# MCU.net
KiCad netlist of a schematic drawn in Altium Designer
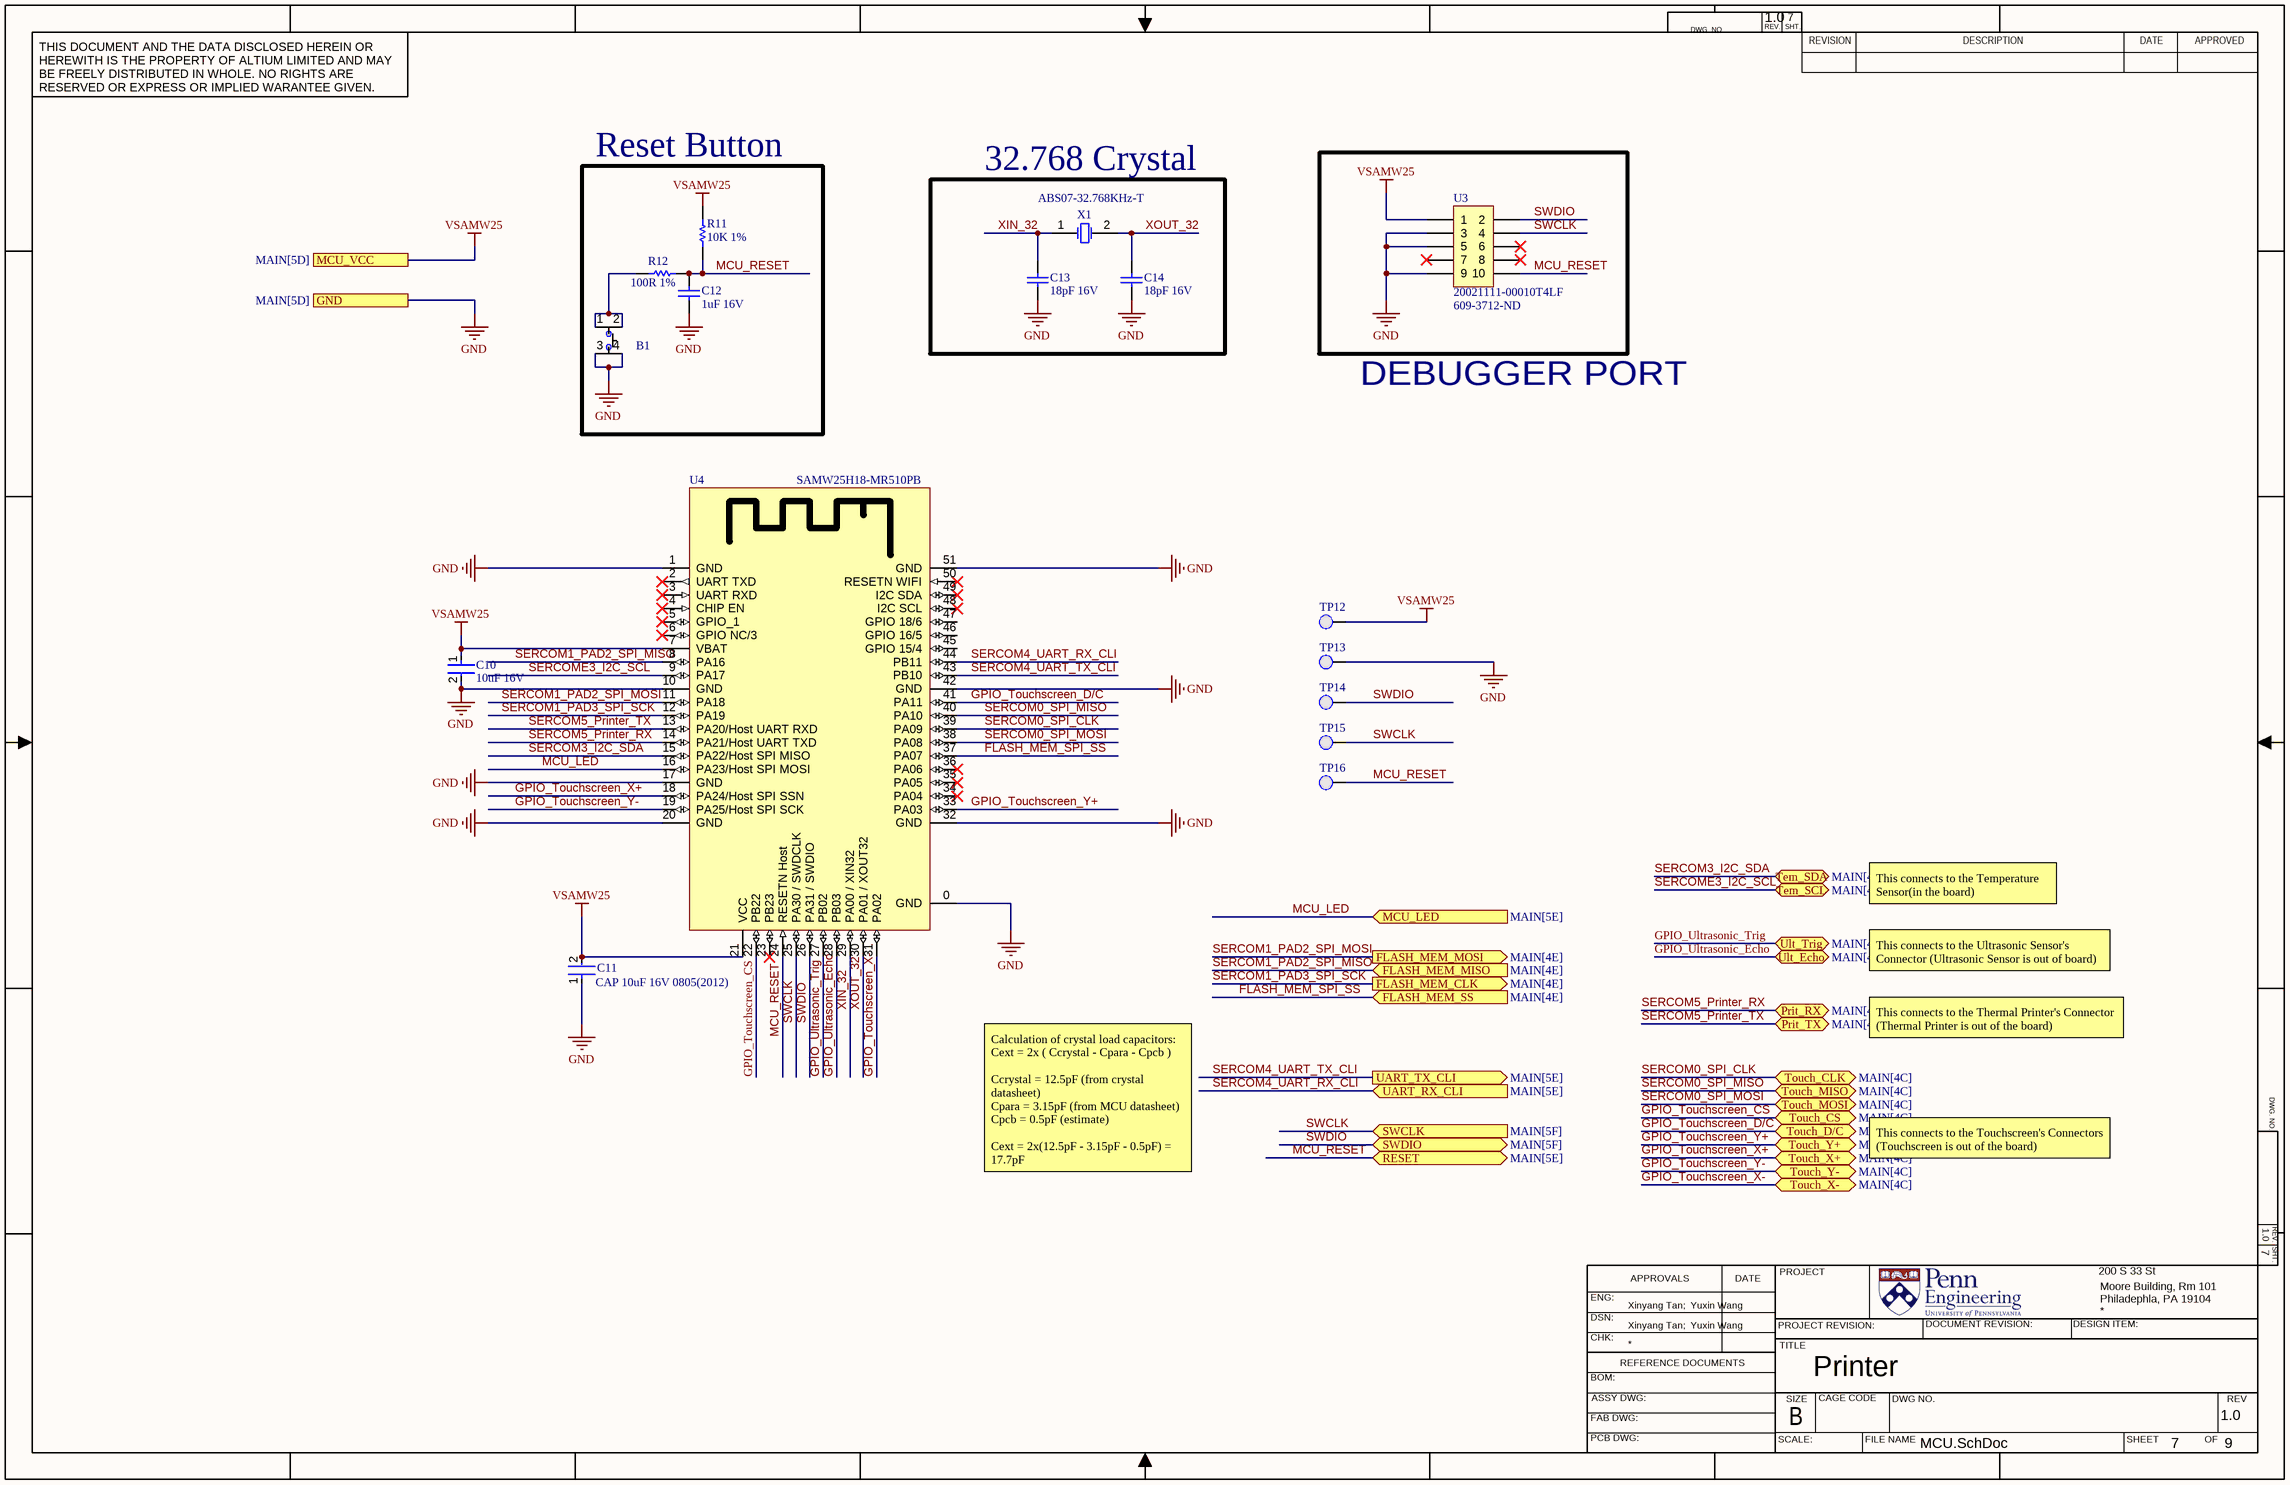
[diagram p0: MCU.SchDoc]

(export (version "E")
  (design (tool "Eeschema 10.0.6"))
  (components
    (comp (ref "B1")
      (value "PTS810 SJK 250 SMTR LFS")
      (footprint "PTS810 SJK 250 SMTR LFS")
      (description "SWITCH TACTILE SPST-NO 0.05A 16V Tactile Switch SPST-NO Top Actuated Surface Mount")
      (fields
        (field (name "MANUFACTURER") "ITT /  C&K Components")
        (field (name "MANUFACTURER PART NUMBER") "PTS810SJK250SMTRLFS")
      )
      (libsource (lib "Schematics") (part "PTS810 SJK 250 SMTR LFS"))
    )
    (comp (ref "C10")
      (value "10uF 16V")
      (footprint "FP-0805-L_2_01_0_2-W_1_25-IPC_A")
      (description "General Purpose Ceramic Capacitor, 0805, 10uF, 10%, X5R, 15%, 16V")
      (fields (field (name "TOLERANCE") "10%") (field (name "VOLTAGE") "16V"))
      (libsource (lib "Altium Content Vault") (part "02cd4be3c70576c341d710602a673aa"))
    )
    (comp (ref "C11")
      (value "CAP 10uF 16V 0805(2012)")
      (footprint "FP-0805-L_2_01_0_2-W_1_25-IPC_A")
      (description "General Purpose Ceramic Capacitor, 0805, 10uF, 10%, X5R, 15%, 16V")
      (fields (field (name "TOLERANCE") "10%") (field (name "VOLTAGE") "16V"))
      (libsource (lib "Altium Content Vault") (part "02cd4be3c70576c341d710602a673aa"))
    )
    (comp (ref "C12")
      (value "1uF 16V")
      (footprint "CAPC0603(1608)100_N")
      (description "CAP 1uF 16V ±5% 0603 (1608 Metric) Thickness 1mm SMD")
      (fields (field (name "TOLERANCE") "Â±5%"))
      (libsource (lib "Altium Content Vault") (part "CAP"))
    )
    (comp (ref "C13")
      (value "18pF 16V")
      (footprint "CAPC0603(1608)100_N")
      (description "CAP 18pF 16V ±5% 0603 (1608 Metric) Thickness 1mm SMD")
      (fields (field (name "TOLERANCE") "Â±5%"))
      (libsource (lib "Altium Content Vault") (part "CAP"))
    )
    (comp (ref "C14")
      (value "18pF 16V")
      (footprint "CAPC0603(1608)100_N")
      (description "CAP 18pF 16V ±5% 0603 (1608 Metric) Thickness 1mm SMD")
      (fields (field (name "TOLERANCE") "Â±5%"))
      (libsource (lib "Altium Content Vault") (part "CAP"))
    )
    (comp (ref "R11")
      (value "10K 1%")
      (footprint "RESC0603(1608)_N")
      (description "10K 0.1W 1% 0603 (1608 Metric)  SMD")
      (fields (field (name "POWER") "0.1 W") (field (name "TOLERANCE") "1 %"))
      (libsource (lib "Altium Content Vault") (part "RES"))
    )
    (comp (ref "R12")
      (value "100R 1%")
      (footprint "RESC0603(1608)_N")
      (description "100R 0.1W 1% 0603 (1608 Metric)  SMD")
      (fields (field (name "TOLERANCE") "1 %") (field (name "POWER") "0.1 W"))
      (libsource (lib "Altium Content Vault") (part "RES"))
    )
    (comp (ref "TP12")
      (value "0.1\" Pad")
      (footprint "PCBComponent")
      (libsource (lib "Schematics") (part "0.1{dblquote} Pad-A.4"))
    )
    (comp (ref "TP13")
      (value "0.1\" Pad")
      (footprint "PCBComponent")
      (libsource (lib "Schematics") (part "0.1{dblquote} Pad-A.4"))
    )
    (comp (ref "TP14")
      (value "0.1\" Pad")
      (footprint "PCBComponent")
      (libsource (lib "Schematics") (part "0.1{dblquote} Pad-A.4"))
    )
    (comp (ref "TP15")
      (value "0.1\" Pad")
      (footprint "PCBComponent")
      (libsource (lib "Schematics") (part "0.1{dblquote} Pad-A.4"))
    )
    (comp (ref "TP16")
      (value "0.1\" Pad")
      (footprint "PCBComponent")
      (libsource (lib "Schematics") (part "0.1{dblquote} Pad-A.4"))
    )
    (comp (ref "U3")
      (value "20021111-00010T4LF")
      (footprint "20021111-00010T4LF")
      (description "CONN HEADER 10POS UNSHD VERT T/H")
      (fields
        (field (name "MANUFACTURER") "Amphenol / FCI")
        (field (name "SUPPLIER PART NUMBER 1") "609-3712-ND")
      )
      (libsource (lib "Schematics") (part "20021111-00010T4LF"))
    )
    (comp (ref "U4")
      (value "SAMW25H18-MR510PB")
      (footprint "SAMW25H18-MR510PB")
      (description "RF TXRX MODULE WIFI TRACE ANT")
      (fields
        (field (name "MANUFACTURER") "Atmel")
        (field (name "MANUFACTURER PART NUMBER") "ATSAMW25H18-MR510PB")
      )
      (libsource (lib "Schematics") (part "SAMW25H18-MR510PB"))
    )
    (comp (ref "X1")
      (value "ABS07-32.768KHz-T")
      (footprint "ABRA-ABS07-2_V")
      (description "Crystal, 32.768 kHz, 12.5 pF, -40 to 85 degC, SMD Low Profile 3.2 x 1.5 x 0.9 mm, Tape and Reel")
      (fields (field (name "MANUFACTURER") "Abracon"))
      (libsource (lib "Altium Content Vault") (part "ABRA-ABS07-2"))
    )
  )
  (nets
    (net (code "1") (name "/FLASH_MEM_SPI_SS") (class "Default")
      (node (ref "U4") (pin "37") (pinfunction "PA07_37") (pintype "bidirectional"))
    )
    (net (code "2") (name "/GPIO_Touchscreen_CS") (class "Default")
      (node (ref "U4") (pin "22") (pinfunction "PB22_22") (pintype "bidirectional"))
    )
    (net (code "3") (name "/GPIO_Touchscreen_D{slash}C") (class "Default")
      (node (ref "U4") (pin "41") (pinfunction "PA11_41") (pintype "bidirectional"))
    )
    (net (code "4") (name "/GPIO_Touchscreen_X+") (class "Default")
      (node (ref "U4") (pin "18") (pinfunction "PA24/Host_SPI_SSN_18") (pintype "bidirectional"))
    )
    (net (code "5") (name "/GPIO_Touchscreen_X-") (class "Default")
      (node (ref "U4") (pin "31") (pinfunction "PA02_31") (pintype "bidirectional"))
    )
    (net (code "6") (name "/GPIO_Touchscreen_Y+") (class "Default")
      (node (ref "U4") (pin "33") (pinfunction "PA03_33") (pintype "bidirectional"))
    )
    (net (code "7") (name "/GPIO_Touchscreen_Y-") (class "Default")
      (node (ref "U4") (pin "19") (pinfunction "PA25/Host_SPI_SCK_19") (pintype "bidirectional"))
    )
    (net (code "8") (name "/GPIO_Ultrasonic_Echo") (class "Default")
      (node (ref "U4") (pin "28") (pinfunction "PB03_28") (pintype "bidirectional"))
    )
    (net (code "9") (name "/GPIO_Ultrasonic_Trig") (class "Default")
      (node (ref "U4") (pin "27") (pinfunction "PB02_27") (pintype "bidirectional"))
    )
    (net (code "10") (name "/MCU_LED") (class "Default")
      (node (ref "U4") (pin "16") (pinfunction "PA23/Host_SPI_MOSI_16") (pintype "bidirectional"))
    )
    (net (code "11") (name "/MCU_RESET") (class "Default")
      (node (ref "C12") (pin "2") (pinfunction "2_2") (pintype "passive"))
      (node (ref "R11") (pin "1") (pinfunction "1_1") (pintype "passive"))
      (node (ref "R12") (pin "2") (pinfunction "2_2") (pintype "passive"))
      (node (ref "TP16") (pin "1") (pinfunction "PAD_1") (pintype "passive"))
      (node (ref "U3") (pin "10") (pinfunction "10_10") (pintype "passive"))
      (node (ref "U4") (pin "24") (pinfunction "RESETN_Host_24") (pintype "input"))
    )
    (net (code "12") (name "/SERCOM0_SPI_CLK") (class "Default")
      (node (ref "U4") (pin "39") (pinfunction "PA09_39") (pintype "bidirectional"))
    )
    (net (code "13") (name "/SERCOM0_SPI_MISO") (class "Default")
      (node (ref "U4") (pin "40") (pinfunction "PA10_40") (pintype "bidirectional"))
    )
    (net (code "14") (name "/SERCOM0_SPI_MOSI") (class "Default")
      (node (ref "U4") (pin "38") (pinfunction "PA08_38") (pintype "bidirectional"))
    )
    (net (code "15") (name "/SERCOM1_PAD2_SPI_MISO") (class "Default")
      (node (ref "U4") (pin "8") (pinfunction "PA16_8") (pintype "bidirectional"))
    )
    (net (code "16") (name "/SERCOM1_PAD2_SPI_MOSI") (class "Default")
      (node (ref "U4") (pin "11") (pinfunction "PA18_11") (pintype "bidirectional"))
    )
    (net (code "17") (name "/SERCOM1_PAD3_SPI_SCK") (class "Default")
      (node (ref "U4") (pin "12") (pinfunction "PA19_12") (pintype "bidirectional"))
    )
    (net (code "18") (name "/SERCOM3_I2C_SDA") (class "Default")
      (node (ref "U4") (pin "15") (pinfunction "PA22/Host_SPI_MISO_15") (pintype "bidirectional"))
    )
    (net (code "19") (name "/SERCOM4_UART_RX_CLI") (class "Default")
      (node (ref "U4") (pin "44") (pinfunction "PB11_44") (pintype "bidirectional"))
    )
    (net (code "20") (name "/SERCOM4_UART_TX_CLI") (class "Default")
      (node (ref "U4") (pin "43") (pinfunction "PB10_43") (pintype "bidirectional"))
    )
    (net (code "21") (name "/SERCOM5_Printer_RX") (class "Default")
      (node (ref "U4") (pin "14") (pinfunction "PA21/Host_UART_TXD_14") (pintype "bidirectional"))
    )
    (net (code "22") (name "/SERCOM5_Printer_TX") (class "Default")
      (node (ref "U4") (pin "13") (pinfunction "PA20/Host_UART_RXD_13") (pintype "bidirectional"))
    )
    (net (code "23") (name "/SERCOME3_I2C_SCL") (class "Default")
      (node (ref "U4") (pin "9") (pinfunction "PA17_9") (pintype "bidirectional"))
    )
    (net (code "24") (name "/SWCLK") (class "Default")
      (node (ref "TP15") (pin "1") (pinfunction "PAD_1") (pintype "passive"))
      (node (ref "U3") (pin "4") (pinfunction "4_4") (pintype "passive"))
      (node (ref "U4") (pin "25") (pinfunction "PA30_/_SWDCLK_25") (pintype "bidirectional"))
    )
    (net (code "25") (name "/SWDIO") (class "Default")
      (node (ref "TP14") (pin "1") (pinfunction "PAD_1") (pintype "passive"))
      (node (ref "U3") (pin "2") (pinfunction "2_2") (pintype "passive"))
      (node (ref "U4") (pin "26") (pinfunction "PA31_/_SWDIO_26") (pintype "bidirectional"))
    )
    (net (code "26") (name "/XIN_32") (class "Default")
      (node (ref "C13") (pin "2") (pinfunction "2_2") (pintype "passive"))
      (node (ref "U4") (pin "29") (pinfunction "PA00_/_XIN32_29") (pintype "bidirectional"))
      (node (ref "X1") (pin "1") (pinfunction "X1_1") (pintype "passive"))
    )
    (net (code "27") (name "/XOUT_32") (class "Default")
      (node (ref "C14") (pin "2") (pinfunction "2_2") (pintype "passive"))
      (node (ref "U4") (pin "30") (pinfunction "PA01_/_XOUT32_30") (pintype "bidirectional"))
      (node (ref "X1") (pin "2") (pinfunction "X2_2") (pintype "passive"))
    )
    (net (code "28") (name "GND") (class "Default")
      (node (ref "B1") (pin "3") (pinfunction "3_3") (pintype "power_in"))
      (node (ref "B1") (pin "4") (pinfunction "4_4") (pintype "power_in"))
      (node (ref "C10") (pin "2") (pinfunction "2_2") (pintype "passive"))
      (node (ref "C11") (pin "1") (pinfunction "1_1") (pintype "passive"))
      (node (ref "C12") (pin "1") (pinfunction "1_1") (pintype "passive"))
      (node (ref "C13") (pin "1") (pinfunction "1_1") (pintype "passive"))
      (node (ref "C14") (pin "1") (pinfunction "1_1") (pintype "passive"))
      (node (ref "TP13") (pin "1") (pinfunction "PAD_1") (pintype "passive"))
      (node (ref "U3") (pin "3") (pinfunction "3_3") (pintype "passive"))
      (node (ref "U3") (pin "5") (pinfunction "5_5") (pintype "passive"))
      (node (ref "U3") (pin "9") (pinfunction "9_9") (pintype "passive"))
      (node (ref "U4") (pin "0") (pinfunction "GND_0") (pintype "power_in"))
      (node (ref "U4") (pin "1") (pinfunction "GND_1") (pintype "power_in"))
      (node (ref "U4") (pin "10") (pinfunction "GND_10") (pintype "power_in"))
      (node (ref "U4") (pin "17") (pinfunction "GND_17") (pintype "power_in"))
      (node (ref "U4") (pin "20") (pinfunction "GND_20") (pintype "power_in"))
      (node (ref "U4") (pin "32") (pinfunction "GND_32") (pintype "power_in"))
      (node (ref "U4") (pin "42") (pinfunction "GND_42") (pintype "power_in"))
      (node (ref "U4") (pin "51") (pinfunction "GND_51") (pintype "power_in"))
    )
    (net (code "29") (name "Net-(B1-Pad1)") (class "Default")
      (node (ref "B1") (pin "1") (pinfunction "1_1") (pintype "power_in"))
      (node (ref "B1") (pin "2") (pinfunction "2_2") (pintype "power_in"))
      (node (ref "R12") (pin "1") (pinfunction "1_1") (pintype "passive"))
    )
    (net (code "30") (name "VSAMW25") (class "Default")
      (node (ref "C10") (pin "1") (pinfunction "1_1") (pintype "passive"))
      (node (ref "C11") (pin "2") (pinfunction "2_2") (pintype "passive"))
      (node (ref "R11") (pin "2") (pinfunction "2_2") (pintype "passive"))
      (node (ref "TP12") (pin "1") (pinfunction "PAD_1") (pintype "passive"))
      (node (ref "U3") (pin "1") (pinfunction "1_1") (pintype "passive"))
      (node (ref "U4") (pin "21") (pinfunction "VCC_21") (pintype "power_in"))
      (node (ref "U4") (pin "7") (pinfunction "VBAT_7") (pintype "power_in"))
    )
    (net (code "31") (name "unconnected-(U3-Pad6)") (class "Default")
      (node (ref "U3") (pin "6") (pinfunction "6_6") (pintype "passive+no_connect"))
    )
    (net (code "32") (name "unconnected-(U3-Pad7)") (class "Default")
      (node (ref "U3") (pin "7") (pinfunction "7_7") (pintype "passive+no_connect"))
    )
    (net (code "33") (name "unconnected-(U3-Pad8)") (class "Default")
      (node (ref "U3") (pin "8") (pinfunction "8_8") (pintype "passive+no_connect"))
    )
    (net (code "34") (name "unconnected-(U4-CHIP_EN-Pad4)") (class "Default")
      (node (ref "U4") (pin "4") (pinfunction "CHIP_EN_4") (pintype "input+no_connect"))
    )
    (net (code "35") (name "unconnected-(U4-GPIO_1-Pad5)") (class "Default")
      (node (ref "U4") (pin "5") (pinfunction "GPIO_1_5") (pintype "bidirectional+no_connect"))
    )
    (net (code "36") (name "unconnected-(U4-GPIO_15{slash}4-Pad45)") (class "Default")
      (node (ref "U4") (pin "45") (pinfunction "GPIO_15/4_45") (pintype "bidirectional"))
    )
    (net (code "37") (name "unconnected-(U4-GPIO_16{slash}5-Pad46)") (class "Default")
      (node (ref "U4") (pin "46") (pinfunction "GPIO_16/5_46") (pintype "bidirectional"))
    )
    (net (code "38") (name "unconnected-(U4-GPIO_18{slash}6-Pad47)") (class "Default")
      (node (ref "U4") (pin "47") (pinfunction "GPIO_18/6_47") (pintype "bidirectional"))
    )
    (net (code "39") (name "unconnected-(U4-GPIO_NC{slash}3-Pad6)") (class "Default")
      (node (ref "U4") (pin "6") (pinfunction "GPIO_NC/3_6") (pintype "bidirectional+no_connect"))
    )
    (net (code "40") (name "unconnected-(U4-I2C_SCL-Pad48)") (class "Default")
      (node (ref "U4") (pin "48") (pinfunction "I2C_SCL_48") (pintype "bidirectional+no_connect"))
    )
    (net (code "41") (name "unconnected-(U4-I2C_SDA-Pad49)") (class "Default")
      (node (ref "U4") (pin "49") (pinfunction "I2C_SDA_49") (pintype "bidirectional+no_connect"))
    )
    (net (code "42") (name "unconnected-(U4-PA04-Pad34)") (class "Default")
      (node (ref "U4") (pin "34") (pinfunction "PA04_34") (pintype "bidirectional+no_connect"))
    )
    (net (code "43") (name "unconnected-(U4-PA05-Pad35)") (class "Default")
      (node (ref "U4") (pin "35") (pinfunction "PA05_35") (pintype "bidirectional+no_connect"))
    )
    (net (code "44") (name "unconnected-(U4-PA06-Pad36)") (class "Default")
      (node (ref "U4") (pin "36") (pinfunction "PA06_36") (pintype "bidirectional+no_connect"))
    )
    (net (code "45") (name "unconnected-(U4-PB23-Pad23)") (class "Default")
      (node (ref "U4") (pin "23") (pinfunction "PB23_23") (pintype "bidirectional+no_connect"))
    )
    (net (code "46") (name "unconnected-(U4-RESETN_WIFI-Pad50)") (class "Default")
      (node (ref "U4") (pin "50") (pinfunction "RESETN_WIFI_50") (pintype "input+no_connect"))
    )
    (net (code "47") (name "unconnected-(U4-UART_RXD-Pad3)") (class "Default")
      (node (ref "U4") (pin "3") (pinfunction "UART_RXD_3") (pintype "input+no_connect"))
    )
    (net (code "48") (name "unconnected-(U4-UART_TXD-Pad2)") (class "Default")
      (node (ref "U4") (pin "2") (pinfunction "UART_TXD_2") (pintype "output+no_connect"))
    )
  )
)
